# HM-10_Breakout.net
KiCad netlist of a schematic drawn in EAGLE
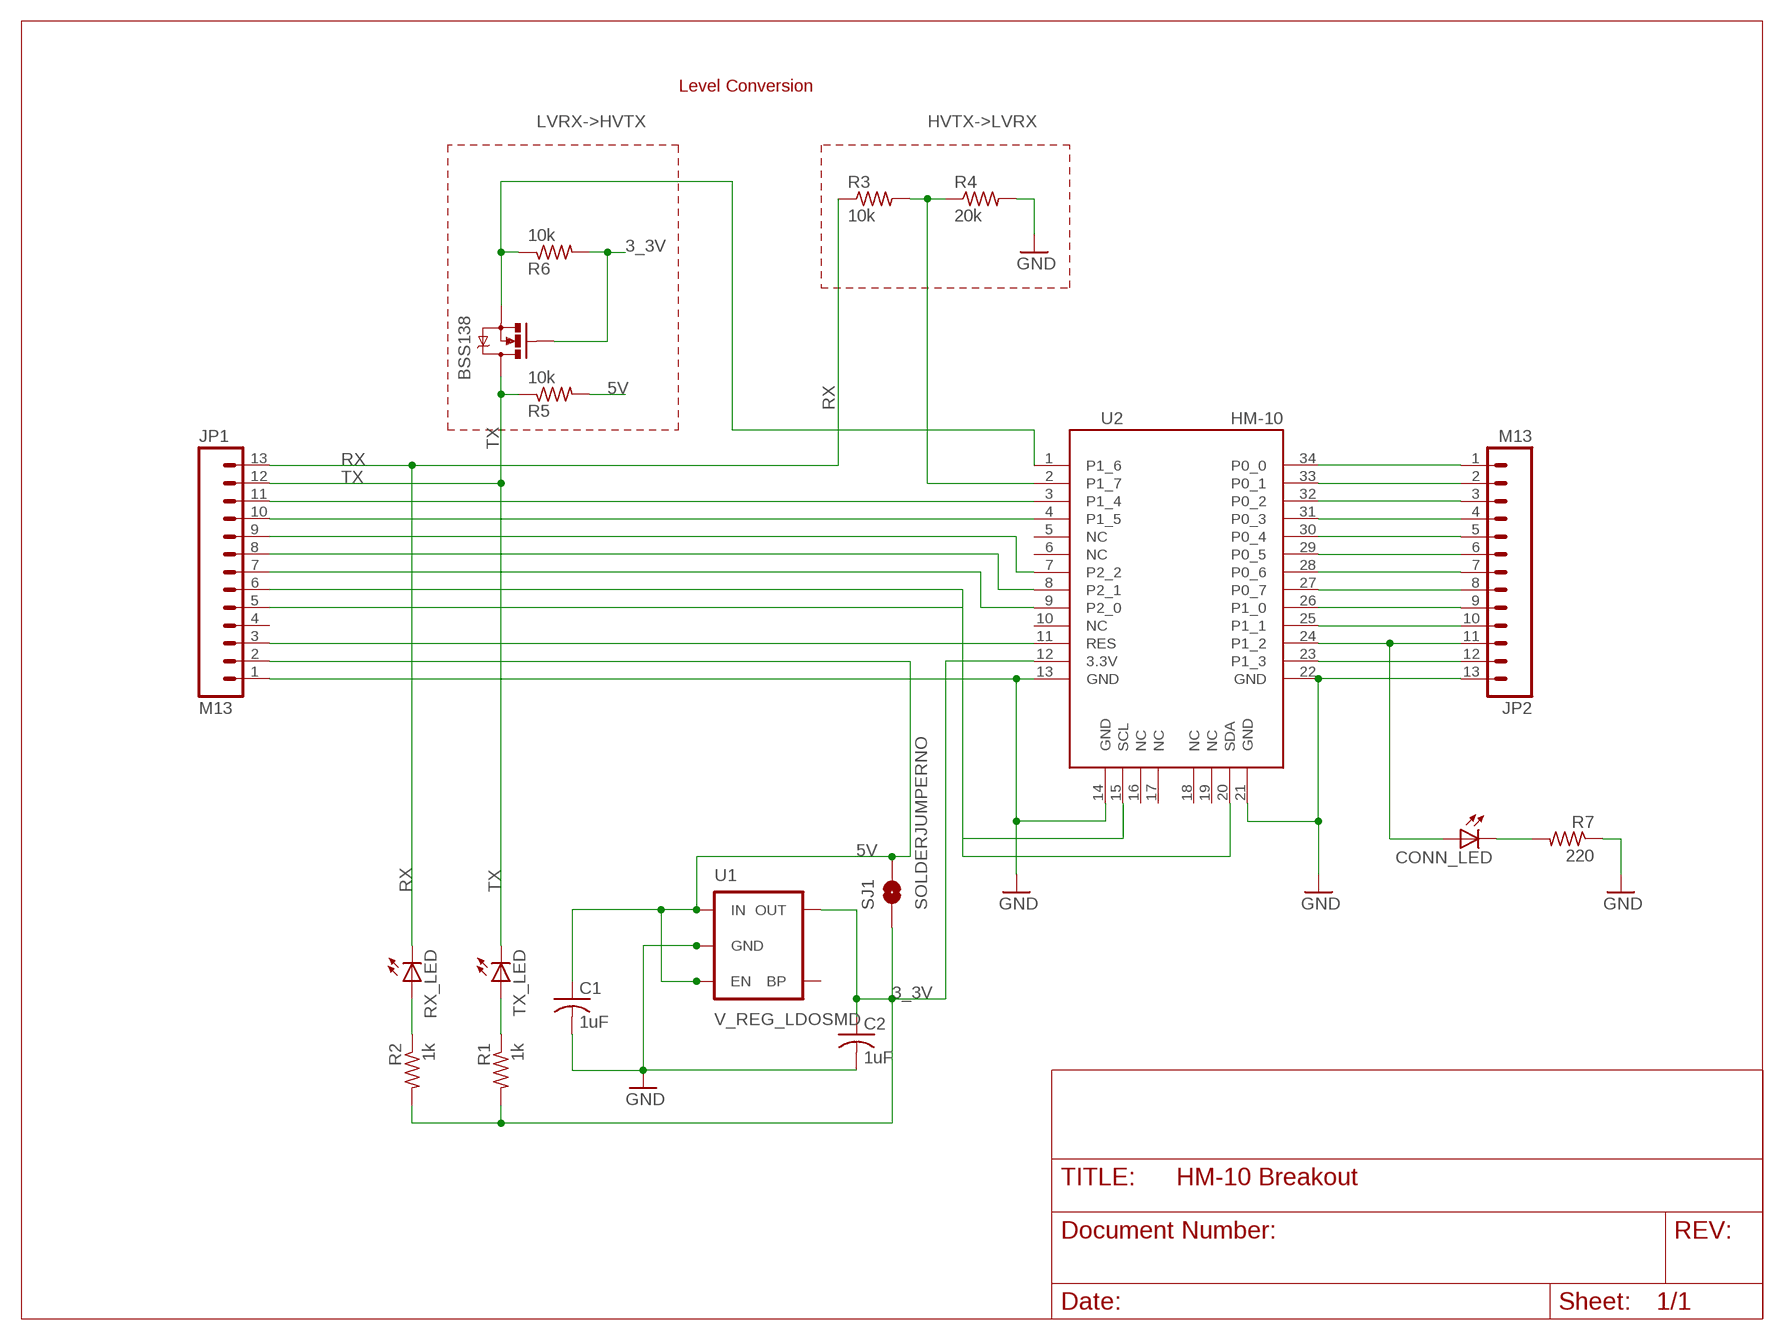
[diagram p0: schematic, sheet 1]

(export (version "E")
  (design (tool "Eeschema 10.0.6"))
  (components
    (comp (ref "BSS138")
      (value "MOSFET-NCHANNELSMD")
      (footprint "eagle-import:SOT23-3")
      (libsource (lib "eagle-import") (part "MOSFET-NCHANNELSMD"))
    )
    (comp (ref "C1")
      (value "1uF")
      (footprint "eagle-import:C0805K")
      (libsource (lib "eagle-import") (part "C-USC0805K"))
    )
    (comp (ref "C2")
      (value "1uF")
      (footprint "eagle-import:C0805K")
      (libsource (lib "eagle-import") (part "C-USC0805K"))
    )
    (comp (ref "CONN_LED")
      (value "LED0603")
      (footprint "eagle-import:LED-0603")
      (libsource (lib "eagle-import") (part "LED0603"))
    )
    (comp (ref "JP1")
      (value "M13")
      (footprint "eagle-import:1X13")
      (libsource (lib "eagle-import") (part "M13"))
    )
    (comp (ref "JP2")
      (value "M13")
      (footprint "eagle-import:1X13")
      (libsource (lib "eagle-import") (part "M13"))
    )
    (comp (ref "R1")
      (value "1k")
      (footprint "eagle-import:M0805")
      (libsource (lib "eagle-import") (part "R-US_M0805"))
    )
    (comp (ref "R2")
      (value "1k")
      (footprint "eagle-import:M0805")
      (libsource (lib "eagle-import") (part "R-US_M0805"))
    )
    (comp (ref "R3")
      (value "10k")
      (footprint "eagle-import:M0805")
      (libsource (lib "eagle-import") (part "R-US_M0805"))
    )
    (comp (ref "R4")
      (value "20k")
      (footprint "eagle-import:M0805")
      (libsource (lib "eagle-import") (part "R-US_M0805"))
    )
    (comp (ref "R5")
      (value "10k")
      (footprint "eagle-import:M0805")
      (libsource (lib "eagle-import") (part "R-US_M0805"))
    )
    (comp (ref "R6")
      (value "10k")
      (footprint "eagle-import:M0805")
      (libsource (lib "eagle-import") (part "R-US_M0805"))
    )
    (comp (ref "R7")
      (value "220")
      (footprint "eagle-import:M0805")
      (libsource (lib "eagle-import") (part "R-US_M0805"))
    )
    (comp (ref "RX_LED")
      (value "LED0603")
      (footprint "eagle-import:LED-0603")
      (libsource (lib "eagle-import") (part "LED0603"))
    )
    (comp (ref "SJ1")
      (value "SOLDERJUMPERNO")
      (footprint "eagle-import:SJ_2S-NO")
      (libsource (lib "eagle-import") (part "SOLDERJUMPERNO"))
    )
    (comp (ref "TX_LED")
      (value "LED0603")
      (footprint "eagle-import:LED-0603")
      (libsource (lib "eagle-import") (part "LED0603"))
    )
    (comp (ref "U1")
      (value "V_REG_LDOSMD")
      (footprint "eagle-import:SOT23-5")
      (libsource (lib "eagle-import") (part "V_REG_LDOSMD"))
    )
    (comp (ref "U2")
      (value "HM-10")
      (footprint "eagle-import:HM-10")
      (libsource (lib "eagle-import") (part "HM-10"))
    )
  )
  (nets
    (net (code "1") (name "/3_3V") (class "Default")
      (node (ref "BSS138") (pin "1") (pinfunction "G_1") (pintype "passive"))
      (node (ref "C2") (pin "1") (pinfunction "1_1") (pintype "passive"))
      (node (ref "R1") (pin "2") (pinfunction "2_2") (pintype "passive"))
      (node (ref "R2") (pin "2") (pinfunction "2_2") (pintype "passive"))
      (node (ref "R6") (pin "2") (pinfunction "2_2") (pintype "passive"))
      (node (ref "SJ1") (pin "1") (pinfunction "1_1") (pintype "passive"))
      (node (ref "U1") (pin "5") (pinfunction "OUT_5") (pintype "passive"))
      (node (ref "U2") (pin "12") (pinfunction "3.3V_12") (pintype "bidirectional"))
    )
    (net (code "2") (name "/5V") (class "Default")
      (node (ref "C1") (pin "1") (pinfunction "1_1") (pintype "passive"))
      (node (ref "JP1") (pin "2") (pinfunction "2_2") (pintype "passive"))
      (node (ref "R5") (pin "2") (pinfunction "2_2") (pintype "passive"))
      (node (ref "SJ1") (pin "2") (pinfunction "2_2") (pintype "passive"))
      (node (ref "U1") (pin "1") (pinfunction "IN_1") (pintype "input"))
      (node (ref "U1") (pin "3") (pinfunction "EN_3") (pintype "input"))
    )
    (net (code "3") (name "/HVTX->LVRX") (class "Default")
      (node (ref "R3") (pin "2") (pinfunction "2_2") (pintype "passive"))
      (node (ref "R4") (pin "1") (pinfunction "1_1") (pintype "passive"))
      (node (ref "U2") (pin "2") (pinfunction "P1_7_2") (pintype "bidirectional"))
    )
    (net (code "4") (name "/LVRX->HVTX") (class "Default")
      (node (ref "BSS138") (pin "2") (pinfunction "S_2") (pintype "passive"))
      (node (ref "R6") (pin "1") (pinfunction "1_1") (pintype "passive"))
      (node (ref "U2") (pin "1") (pinfunction "P1_6_1") (pintype "bidirectional"))
    )
    (net (code "5") (name "/RX") (class "Default")
      (node (ref "JP1") (pin "13") (pinfunction "13_13") (pintype "passive"))
      (node (ref "R3") (pin "1") (pinfunction "1_1") (pintype "passive"))
      (node (ref "RX_LED") (pin "C") (pinfunction "C_C") (pintype "passive"))
    )
    (net (code "6") (name "/TX") (class "Default")
      (node (ref "BSS138") (pin "3") (pinfunction "D_3") (pintype "passive"))
      (node (ref "JP1") (pin "12") (pinfunction "12_12") (pintype "passive"))
      (node (ref "R5") (pin "1") (pinfunction "1_1") (pintype "passive"))
      (node (ref "TX_LED") (pin "C") (pinfunction "C_C") (pintype "passive"))
    )
    (net (code "7") (name "GND") (class "Default")
      (node (ref "C1") (pin "2") (pinfunction "2_2") (pintype "passive"))
      (node (ref "C2") (pin "2") (pinfunction "2_2") (pintype "passive"))
      (node (ref "JP1") (pin "1") (pinfunction "1_1") (pintype "passive"))
      (node (ref "JP2") (pin "13") (pinfunction "13_13") (pintype "passive"))
      (node (ref "R4") (pin "2") (pinfunction "2_2") (pintype "passive"))
      (node (ref "R7") (pin "1") (pinfunction "1_1") (pintype "passive"))
      (node (ref "U1") (pin "2") (pinfunction "GND_2") (pintype "input"))
      (node (ref "U2") (pin "13") (pinfunction "GND_13") (pintype "bidirectional"))
      (node (ref "U2") (pin "14") (pinfunction "GND_14") (pintype "bidirectional"))
      (node (ref "U2") (pin "21") (pinfunction "GND_21") (pintype "bidirectional"))
      (node (ref "U2") (pin "22") (pinfunction "GND_22") (pintype "bidirectional"))
    )
    (net (code "8") (name "Net-(CONN_LED-PadC)") (class "Default")
      (node (ref "CONN_LED") (pin "C") (pinfunction "C_C") (pintype "passive"))
      (node (ref "R7") (pin "2") (pinfunction "2_2") (pintype "passive"))
    )
    (net (code "9") (name "Net-(R1-Pad1)") (class "Default")
      (node (ref "R1") (pin "1") (pinfunction "1_1") (pintype "passive"))
      (node (ref "TX_LED") (pin "A") (pinfunction "A_A") (pintype "passive"))
    )
    (net (code "10") (name "Net-(R2-Pad1)") (class "Default")
      (node (ref "R2") (pin "1") (pinfunction "1_1") (pintype "passive"))
      (node (ref "RX_LED") (pin "A") (pinfunction "A_A") (pintype "passive"))
    )
    (net (code "11") (name "Net-(U2-P0_0)") (class "Default")
      (node (ref "JP2") (pin "1") (pinfunction "1_1") (pintype "passive"))
      (node (ref "U2") (pin "34") (pinfunction "P0_0_34") (pintype "bidirectional"))
    )
    (net (code "12") (name "Net-(U2-P0_1)") (class "Default")
      (node (ref "JP2") (pin "2") (pinfunction "2_2") (pintype "passive"))
      (node (ref "U2") (pin "33") (pinfunction "P0_1_33") (pintype "bidirectional"))
    )
    (net (code "13") (name "Net-(U2-P0_2)") (class "Default")
      (node (ref "JP2") (pin "3") (pinfunction "3_3") (pintype "passive"))
      (node (ref "U2") (pin "32") (pinfunction "P0_2_32") (pintype "bidirectional"))
    )
    (net (code "14") (name "Net-(U2-P0_3)") (class "Default")
      (node (ref "JP2") (pin "4") (pinfunction "4_4") (pintype "passive"))
      (node (ref "U2") (pin "31") (pinfunction "P0_3_31") (pintype "bidirectional"))
    )
    (net (code "15") (name "Net-(U2-P0_4)") (class "Default")
      (node (ref "JP2") (pin "5") (pinfunction "5_5") (pintype "passive"))
      (node (ref "U2") (pin "30") (pinfunction "P0_4_30") (pintype "bidirectional"))
    )
    (net (code "16") (name "Net-(U2-P0_5)") (class "Default")
      (node (ref "JP2") (pin "6") (pinfunction "6_6") (pintype "passive"))
      (node (ref "U2") (pin "29") (pinfunction "P0_5_29") (pintype "bidirectional"))
    )
    (net (code "17") (name "Net-(U2-P0_6)") (class "Default")
      (node (ref "JP2") (pin "7") (pinfunction "7_7") (pintype "passive"))
      (node (ref "U2") (pin "28") (pinfunction "P0_6_28") (pintype "bidirectional"))
    )
    (net (code "18") (name "Net-(U2-P0_7)") (class "Default")
      (node (ref "JP2") (pin "8") (pinfunction "8_8") (pintype "passive"))
      (node (ref "U2") (pin "27") (pinfunction "P0_7_27") (pintype "bidirectional"))
    )
    (net (code "19") (name "Net-(U2-P1_0)") (class "Default")
      (node (ref "JP2") (pin "9") (pinfunction "9_9") (pintype "passive"))
      (node (ref "U2") (pin "26") (pinfunction "P1_0_26") (pintype "bidirectional"))
    )
    (net (code "20") (name "Net-(U2-P1_1)") (class "Default")
      (node (ref "JP2") (pin "10") (pinfunction "10_10") (pintype "passive"))
      (node (ref "U2") (pin "25") (pinfunction "P1_1_25") (pintype "bidirectional"))
    )
    (net (code "21") (name "Net-(U2-P1_2)") (class "Default")
      (node (ref "CONN_LED") (pin "A") (pinfunction "A_A") (pintype "passive"))
      (node (ref "JP2") (pin "11") (pinfunction "11_11") (pintype "passive"))
      (node (ref "U2") (pin "24") (pinfunction "P1_2_24") (pintype "bidirectional"))
    )
    (net (code "22") (name "Net-(U2-P1_3)") (class "Default")
      (node (ref "JP2") (pin "12") (pinfunction "12_12") (pintype "passive"))
      (node (ref "U2") (pin "23") (pinfunction "P1_3_23") (pintype "bidirectional"))
    )
    (net (code "23") (name "Net-(U2-P1_4)") (class "Default")
      (node (ref "JP1") (pin "11") (pinfunction "11_11") (pintype "passive"))
      (node (ref "U2") (pin "3") (pinfunction "P1_4_3") (pintype "bidirectional"))
    )
    (net (code "24") (name "Net-(U2-P1_5)") (class "Default")
      (node (ref "JP1") (pin "10") (pinfunction "10_10") (pintype "passive"))
      (node (ref "U2") (pin "4") (pinfunction "P1_5_4") (pintype "bidirectional"))
    )
    (net (code "25") (name "Net-(U2-P2_0)") (class "Default")
      (node (ref "JP1") (pin "7") (pinfunction "7_7") (pintype "passive"))
      (node (ref "U2") (pin "9") (pinfunction "P2_0_9") (pintype "bidirectional"))
    )
    (net (code "26") (name "Net-(U2-P2_1)") (class "Default")
      (node (ref "JP1") (pin "8") (pinfunction "8_8") (pintype "passive"))
      (node (ref "U2") (pin "8") (pinfunction "P2_1_8") (pintype "bidirectional"))
    )
    (net (code "27") (name "Net-(U2-P2_2)") (class "Default")
      (node (ref "JP1") (pin "9") (pinfunction "9_9") (pintype "passive"))
      (node (ref "U2") (pin "7") (pinfunction "P2_2_7") (pintype "bidirectional"))
    )
    (net (code "28") (name "Net-(U2-RES)") (class "Default")
      (node (ref "JP1") (pin "3") (pinfunction "3_3") (pintype "passive"))
      (node (ref "U2") (pin "11") (pinfunction "RES_11") (pintype "bidirectional"))
    )
    (net (code "29") (name "Net-(U2-SCL)") (class "Default")
      (node (ref "JP1") (pin "5") (pinfunction "5_5") (pintype "passive"))
      (node (ref "U2") (pin "15") (pinfunction "SCL_15") (pintype "bidirectional"))
    )
    (net (code "30") (name "Net-(U2-SDA)") (class "Default")
      (node (ref "JP1") (pin "6") (pinfunction "6_6") (pintype "passive"))
      (node (ref "U2") (pin "20") (pinfunction "SDA_20") (pintype "bidirectional"))
    )
    (net (code "31") (name "unconnected-(JP1-Pad4)") (class "Default")
      (node (ref "JP1") (pin "4") (pinfunction "4_4") (pintype "passive"))
    )
    (net (code "32") (name "unconnected-(U1-BP-Pad4)") (class "Default")
      (node (ref "U1") (pin "4") (pinfunction "BP_4") (pintype "input"))
    )
    (net (code "33") (name "unconnected-(U2-NC-Pad5)") (class "Default")
      (node (ref "U2") (pin "5") (pinfunction "NC_5") (pintype "bidirectional"))
    )
    (net (code "34") (name "unconnected-(U2-NC-Pad6)") (class "Default")
      (node (ref "U2") (pin "6") (pinfunction "NC_6") (pintype "bidirectional"))
    )
    (net (code "35") (name "unconnected-(U2-NC-Pad10)") (class "Default")
      (node (ref "U2") (pin "10") (pinfunction "NC_10") (pintype "bidirectional"))
    )
    (net (code "36") (name "unconnected-(U2-NC-Pad16)") (class "Default")
      (node (ref "U2") (pin "16") (pinfunction "NC_16") (pintype "bidirectional"))
    )
    (net (code "37") (name "unconnected-(U2-NC-Pad17)") (class "Default")
      (node (ref "U2") (pin "17") (pinfunction "NC_17") (pintype "bidirectional"))
    )
    (net (code "38") (name "unconnected-(U2-NC-Pad18)") (class "Default")
      (node (ref "U2") (pin "18") (pinfunction "NC_18") (pintype "bidirectional"))
    )
    (net (code "39") (name "unconnected-(U2-NC-Pad19)") (class "Default")
      (node (ref "U2") (pin "19") (pinfunction "NC_19") (pintype "bidirectional"))
    )
  )
)
